# tick-wifi-mk-1_0.net
KiCad netlist of a schematic drawn in EAGLE
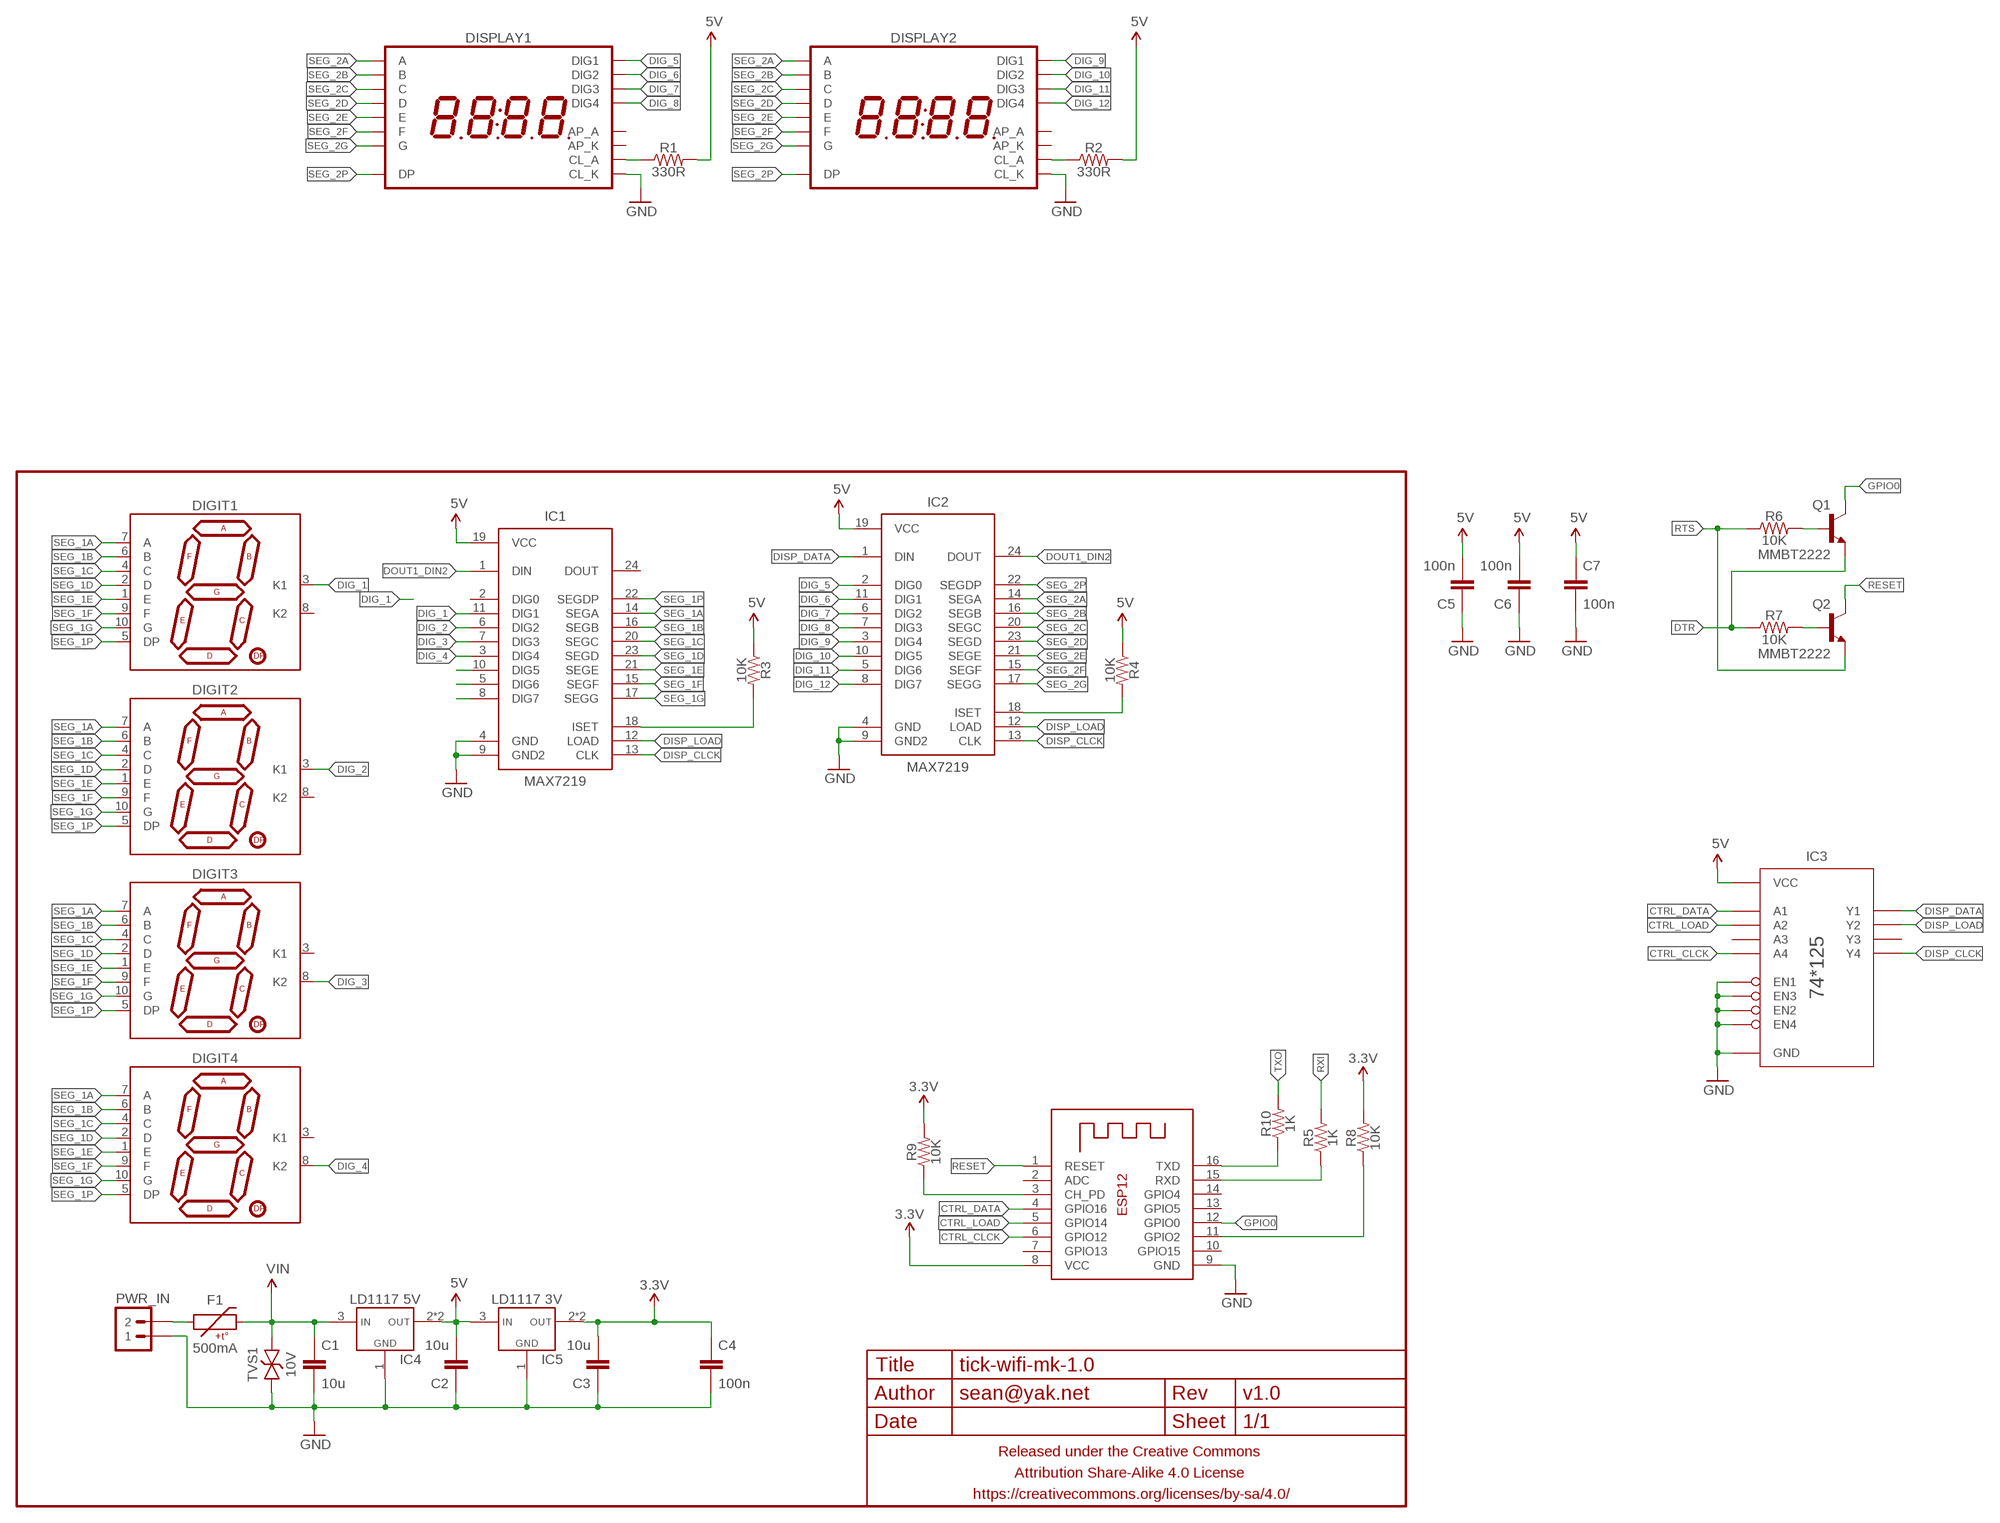
[diagram p0: schematic, sheet 1]

(export (version "E")
  (design (tool "Eeschema 10.0.6"))
  (components
    (comp (ref "C1")
      (value "10u")
      (footprint "eagle-import:C1210")
      (libsource (lib "eagle-import") (part "CAPACITOR-CERAMICC1210"))
    )
    (comp (ref "C2")
      (value "10u")
      (footprint "eagle-import:C1210")
      (libsource (lib "eagle-import") (part "CAPACITOR-CERAMICC1210"))
    )
    (comp (ref "C3")
      (value "10u")
      (footprint "eagle-import:C1210")
      (libsource (lib "eagle-import") (part "CAPACITOR-CERAMICC1210"))
    )
    (comp (ref "C4")
      (value "100n")
      (footprint "eagle-import:C0603")
      (libsource (lib "eagle-import") (part "CAPACITOR-CERAMICC0603"))
    )
    (comp (ref "C5")
      (value "100n")
      (footprint "eagle-import:C0603")
      (libsource (lib "eagle-import") (part "CAPACITOR-CERAMICC0603"))
    )
    (comp (ref "C6")
      (value "100n")
      (footprint "eagle-import:C0603")
      (libsource (lib "eagle-import") (part "CAPACITOR-CERAMICC0603"))
    )
    (comp (ref "C7")
      (value "100n")
      (footprint "eagle-import:C0603")
      (libsource (lib "eagle-import") (part "CAPACITOR-CERAMICC0603"))
    )
    (comp (ref "DIGIT1")
      (value "7SEG_1DIGPTH-25.4MM-BARE")
      (footprint "eagle-import:7SEG_1DIG_25.4MM_NOSILK")
      (libsource (lib "eagle-import") (part "7SEG_1DIGPTH-25.4MM-BARE"))
    )
    (comp (ref "DIGIT2")
      (value "7SEG_1DIGPTH-25.4MM-BARE")
      (footprint "eagle-import:7SEG_1DIG_25.4MM_NOSILK")
      (libsource (lib "eagle-import") (part "7SEG_1DIGPTH-25.4MM-BARE"))
    )
    (comp (ref "DIGIT3")
      (value "7SEG_1DIGPTH-25.4MM-BARE")
      (footprint "eagle-import:7SEG_1DIG_25.4MM_NOSILK")
      (libsource (lib "eagle-import") (part "7SEG_1DIGPTH-25.4MM-BARE"))
    )
    (comp (ref "DIGIT4")
      (value "7SEG_1DIGPTH-25.4MM-BARE")
      (footprint "eagle-import:7SEG_1DIG_25.4MM_NOSILK")
      (libsource (lib "eagle-import") (part "7SEG_1DIGPTH-25.4MM-BARE"))
    )
    (comp (ref "DISPLAY1")
      (value "7SEG_4DIGIT_COLON_APOS")
      (footprint "eagle-import:7SEG_4DIG_10MM")
      (libsource (lib "eagle-import") (part "7SEG_4DIGIT_COLON_APOS"))
    )
    (comp (ref "DISPLAY2")
      (value "7SEG_4DIGIT_COLON_APOS")
      (footprint "eagle-import:7SEG_4DIG_10MM")
      (libsource (lib "eagle-import") (part "7SEG_4DIGIT_COLON_APOS"))
    )
    (comp (ref "F1")
      (value "500mA")
      (footprint "eagle-import:PTC-1210")
      (libsource (lib "eagle-import") (part "PTCPTC-1210"))
    )
    (comp (ref "FRAME1")
      (value "FRAME-LETTERNO_PACKAGE")
      (footprint "eagle-import:DUMMY")
      (fields (field (name "DESIGNER") "sean@yak.net") (field (name "VERSION") "v1.0"))
      (libsource (lib "eagle-import") (part "FRAME-LETTERNO_PACKAGE"))
    )
    (comp (ref "IC1")
      (value "MAX7219")
      (footprint "eagle-import:SO24W")
      (libsource (lib "eagle-import") (part "MAX7219SOIC-W"))
    )
    (comp (ref "IC2")
      (value "MAX7219")
      (footprint "eagle-import:SO24W")
      (libsource (lib "eagle-import") (part "MAX7219SOIC-W"))
    )
    (comp (ref "IC3")
      (value "74HC125")
      (footprint "eagle-import:SO14")
      (libsource (lib "eagle-import") (part "74125SOIC14"))
    )
    (comp (ref "IC4")
      (value "LD1117 5V")
      (footprint "eagle-import:SOT223")
      (libsource (lib "eagle-import") (part "VREG_1117SOT223"))
    )
    (comp (ref "IC5")
      (value "LD1117 3V")
      (footprint "eagle-import:SOT223")
      (libsource (lib "eagle-import") (part "VREG_1117SOT223"))
    )
    (comp (ref "PWR_IN")
      (value "M02PTH-CENTERED-R+")
      (footprint "eagle-import:1X02-CENTER-R+")
      (libsource (lib "eagle-import") (part "M02PTH-CENTERED-R+"))
    )
    (comp (ref "Q1")
      (value "MMBT2222")
      (footprint "eagle-import:SOT23")
      (libsource (lib "eagle-import") (part "TRANSISTOR_NPNMMBT2222A"))
    )
    (comp (ref "Q2")
      (value "MMBT2222")
      (footprint "eagle-import:SOT23")
      (libsource (lib "eagle-import") (part "TRANSISTOR_NPNMMBT2222A"))
    )
    (comp (ref "R1")
      (value "330R")
      (footprint "eagle-import:R0805")
      (libsource (lib "eagle-import") (part "RESISTORR0805"))
    )
    (comp (ref "R2")
      (value "330R")
      (footprint "eagle-import:R0805")
      (libsource (lib "eagle-import") (part "RESISTORR0805"))
    )
    (comp (ref "R3")
      (value "10K")
      (footprint "eagle-import:R0603")
      (libsource (lib "eagle-import") (part "RESISTORR0603"))
    )
    (comp (ref "R4")
      (value "10K")
      (footprint "eagle-import:R0603")
      (libsource (lib "eagle-import") (part "RESISTORR0603"))
    )
    (comp (ref "R5")
      (value "1K")
      (footprint "eagle-import:R0603")
      (libsource (lib "eagle-import") (part "RESISTORR0603"))
    )
    (comp (ref "R6")
      (value "10K")
      (footprint "eagle-import:R0603")
      (libsource (lib "eagle-import") (part "RESISTORR0603"))
    )
    (comp (ref "R7")
      (value "10K")
      (footprint "eagle-import:R0603")
      (libsource (lib "eagle-import") (part "RESISTORR0603"))
    )
    (comp (ref "R8")
      (value "10K")
      (footprint "eagle-import:R0603")
      (libsource (lib "eagle-import") (part "RESISTORR0603"))
    )
    (comp (ref "R9")
      (value "10K")
      (footprint "eagle-import:R0603")
      (libsource (lib "eagle-import") (part "RESISTORR0603"))
    )
    (comp (ref "R10")
      (value "1K")
      (footprint "eagle-import:R0603")
      (libsource (lib "eagle-import") (part "RESISTORR0603"))
    )
    (comp (ref "TVS1")
      (value "10V")
      (footprint "eagle-import:SMA-DIODE-TVS-BIDIR")
      (libsource (lib "eagle-import") (part "TVSSMA"))
    )
    (comp (ref "U1")
      (value "ESP-12")
      (footprint "eagle-import:ESP-12")
      (libsource (lib "eagle-import") (part "ESP-12"))
    )
  )
  (nets
    (net (code "1") (name "3.3V") (class "Default")
      (node (ref "C3") (pin "2") (pinfunction "2_2") (pintype "passive"))
      (node (ref "C4") (pin "1") (pinfunction "1_1") (pintype "passive"))
      (node (ref "IC5") (pin "2") (pinfunction "VOUT_2") (pintype "bidirectional"))
      (node (ref "IC5") (pin "4") (pinfunction "VOUT_4") (pintype "bidirectional"))
      (node (ref "R8") (pin "2") (pinfunction "2_2") (pintype "passive"))
      (node (ref "R9") (pin "2") (pinfunction "2_2") (pintype "passive"))
      (node (ref "U1") (pin "8") (pinfunction "VCC_8") (pintype "power_in"))
    )
    (net (code "2") (name "5V") (class "Default")
      (node (ref "C2") (pin "2") (pinfunction "2_2") (pintype "passive"))
      (node (ref "C5") (pin "2") (pinfunction "2_2") (pintype "passive"))
      (node (ref "C6") (pin "2") (pinfunction "2_2") (pintype "passive"))
      (node (ref "C7") (pin "1") (pinfunction "1_1") (pintype "passive"))
      (node (ref "IC1") (pin "19") (pinfunction "VCC_19") (pintype "bidirectional"))
      (node (ref "IC2") (pin "19") (pinfunction "VCC_19") (pintype "bidirectional"))
      (node (ref "IC3") (pin "14") (pinfunction "VCC_14") (pintype "bidirectional"))
      (node (ref "IC4") (pin "2") (pinfunction "VOUT_2") (pintype "bidirectional"))
      (node (ref "IC4") (pin "4") (pinfunction "VOUT_4") (pintype "bidirectional"))
      (node (ref "IC5") (pin "3") (pinfunction "VIN_3") (pintype "bidirectional"))
      (node (ref "R1") (pin "2") (pinfunction "2_2") (pintype "passive"))
      (node (ref "R2") (pin "2") (pinfunction "2_2") (pintype "passive"))
      (node (ref "R3") (pin "1") (pinfunction "1_1") (pintype "passive"))
      (node (ref "R4") (pin "1") (pinfunction "1_1") (pintype "passive"))
    )
    (net (code "3") (name "CTRL_CLCK") (class "Default")
      (node (ref "IC3") (pin "12") (pinfunction "A4_12") (pintype "bidirectional"))
      (node (ref "U1") (pin "6") (pinfunction "GPIO12_6") (pintype "bidirectional"))
    )
    (net (code "4") (name "CTRL_DATA") (class "Default")
      (node (ref "IC3") (pin "2") (pinfunction "A1_2") (pintype "bidirectional"))
      (node (ref "U1") (pin "4") (pinfunction "GPIO16_4") (pintype "bidirectional"))
    )
    (net (code "5") (name "CTRL_LOAD") (class "Default")
      (node (ref "IC3") (pin "5") (pinfunction "A2_5") (pintype "bidirectional"))
      (node (ref "U1") (pin "5") (pinfunction "GPIO14_5") (pintype "bidirectional"))
    )
    (net (code "6") (name "DIG_1") (class "Default")
      (node (ref "DIGIT1") (pin "3") (pinfunction "K1_3") (pintype "bidirectional"))
      (node (ref "IC1") (pin "11") (pinfunction "DIG1_11") (pintype "bidirectional"))
    )
    (net (code "7") (name "DIG_2") (class "Default")
      (node (ref "DIGIT2") (pin "3") (pinfunction "K1_3") (pintype "bidirectional"))
      (node (ref "IC1") (pin "6") (pinfunction "DIG2_6") (pintype "bidirectional"))
    )
    (net (code "8") (name "DIG_3") (class "Default")
      (node (ref "DIGIT3") (pin "8") (pinfunction "K2_8") (pintype "bidirectional"))
      (node (ref "IC1") (pin "7") (pinfunction "DIG3_7") (pintype "bidirectional"))
    )
    (net (code "9") (name "DIG_4") (class "Default")
      (node (ref "DIGIT4") (pin "8") (pinfunction "K2_8") (pintype "bidirectional"))
      (node (ref "IC1") (pin "3") (pinfunction "DIG4_3") (pintype "bidirectional"))
    )
    (net (code "10") (name "DIG_5") (class "Default")
      (node (ref "DISPLAY1") (pin "1") (pinfunction "DIG1_1") (pintype "passive"))
      (node (ref "IC2") (pin "2") (pinfunction "DIG0_2") (pintype "bidirectional"))
    )
    (net (code "11") (name "DIG_6") (class "Default")
      (node (ref "DISPLAY1") (pin "2") (pinfunction "DIG2_2") (pintype "passive"))
      (node (ref "IC2") (pin "11") (pinfunction "DIG1_11") (pintype "bidirectional"))
    )
    (net (code "12") (name "DIG_7") (class "Default")
      (node (ref "DISPLAY1") (pin "6") (pinfunction "DIG3_6") (pintype "passive"))
      (node (ref "IC2") (pin "6") (pinfunction "DIG2_6") (pintype "bidirectional"))
    )
    (net (code "13") (name "DIG_8") (class "Default")
      (node (ref "DISPLAY1") (pin "8") (pinfunction "DIG4_8") (pintype "passive"))
      (node (ref "IC2") (pin "7") (pinfunction "DIG3_7") (pintype "bidirectional"))
    )
    (net (code "14") (name "DIG_9") (class "Default")
      (node (ref "DISPLAY2") (pin "1") (pinfunction "DIG1_1") (pintype "passive"))
      (node (ref "IC2") (pin "3") (pinfunction "DIG4_3") (pintype "bidirectional"))
    )
    (net (code "15") (name "DIG_10") (class "Default")
      (node (ref "DISPLAY2") (pin "2") (pinfunction "DIG2_2") (pintype "passive"))
      (node (ref "IC2") (pin "10") (pinfunction "DIG5_10") (pintype "bidirectional"))
    )
    (net (code "16") (name "DIG_11") (class "Default")
      (node (ref "DISPLAY2") (pin "6") (pinfunction "DIG3_6") (pintype "passive"))
      (node (ref "IC2") (pin "5") (pinfunction "DIG6_5") (pintype "bidirectional"))
    )
    (net (code "17") (name "DIG_12") (class "Default")
      (node (ref "DISPLAY2") (pin "8") (pinfunction "DIG4_8") (pintype "passive"))
      (node (ref "IC2") (pin "8") (pinfunction "DIG7_8") (pintype "bidirectional"))
    )
    (net (code "18") (name "DISP_CLCK") (class "Default")
      (node (ref "IC1") (pin "13") (pinfunction "CLK_13") (pintype "bidirectional"))
      (node (ref "IC2") (pin "13") (pinfunction "CLK_13") (pintype "bidirectional"))
      (node (ref "IC3") (pin "11") (pinfunction "Y4_11") (pintype "bidirectional"))
    )
    (net (code "19") (name "DISP_DATA") (class "Default")
      (node (ref "IC2") (pin "1") (pinfunction "DIN_1") (pintype "bidirectional"))
      (node (ref "IC3") (pin "3") (pinfunction "Y1_3") (pintype "bidirectional"))
    )
    (net (code "20") (name "DISP_LOAD") (class "Default")
      (node (ref "IC1") (pin "12") (pinfunction "LOAD_12") (pintype "bidirectional"))
      (node (ref "IC2") (pin "12") (pinfunction "LOAD_12") (pintype "bidirectional"))
      (node (ref "IC3") (pin "6") (pinfunction "Y2_6") (pintype "bidirectional"))
    )
    (net (code "21") (name "DOUT1_DIN2") (class "Default")
      (node (ref "IC1") (pin "1") (pinfunction "DIN_1") (pintype "bidirectional"))
      (node (ref "IC2") (pin "24") (pinfunction "DOUT_24") (pintype "bidirectional"))
    )
    (net (code "22") (name "DTR") (class "Default")
      (node (ref "Q1") (pin "2") (pinfunction "E_2") (pintype "passive"))
      (node (ref "R7") (pin "1") (pinfunction "1_1") (pintype "passive"))
    )
    (net (code "23") (name "GND") (class "Default")
      (node (ref "C1") (pin "2") (pinfunction "2_2") (pintype "passive"))
      (node (ref "C2") (pin "1") (pinfunction "1_1") (pintype "passive"))
      (node (ref "C3") (pin "1") (pinfunction "1_1") (pintype "passive"))
      (node (ref "C4") (pin "2") (pinfunction "2_2") (pintype "passive"))
      (node (ref "C5") (pin "1") (pinfunction "1_1") (pintype "passive"))
      (node (ref "C6") (pin "1") (pinfunction "1_1") (pintype "passive"))
      (node (ref "C7") (pin "2") (pinfunction "2_2") (pintype "passive"))
      (node (ref "DISPLAY1") (pin "12") (pinfunction "CL_K_12") (pintype "passive"))
      (node (ref "DISPLAY2") (pin "12") (pinfunction "CL_K_12") (pintype "passive"))
      (node (ref "IC1") (pin "4") (pinfunction "GND_4") (pintype "bidirectional"))
      (node (ref "IC1") (pin "9") (pinfunction "GND2_9") (pintype "bidirectional"))
      (node (ref "IC2") (pin "4") (pinfunction "GND_4") (pintype "bidirectional"))
      (node (ref "IC2") (pin "9") (pinfunction "GND2_9") (pintype "bidirectional"))
      (node (ref "IC3") (pin "1") (pinfunction "EN1_1") (pintype "bidirectional"))
      (node (ref "IC3") (pin "10") (pinfunction "EN3_10") (pintype "bidirectional"))
      (node (ref "IC3") (pin "13") (pinfunction "EN4_13") (pintype "bidirectional"))
      (node (ref "IC3") (pin "4") (pinfunction "EN2_4") (pintype "bidirectional"))
      (node (ref "IC3") (pin "7") (pinfunction "GND_7") (pintype "bidirectional"))
      (node (ref "IC4") (pin "1") (pinfunction "GND_1") (pintype "bidirectional"))
      (node (ref "IC5") (pin "1") (pinfunction "GND_1") (pintype "bidirectional"))
      (node (ref "PWR_IN") (pin "1") (pinfunction "1_1") (pintype "passive"))
      (node (ref "TVS1") (pin "1") (pinfunction "1_1") (pintype "passive"))
      (node (ref "U1") (pin "9") (pinfunction "GND_9") (pintype "power_in"))
    )
    (net (code "24") (name "GPIO0") (class "Default")
      (node (ref "Q1") (pin "3") (pinfunction "C_3") (pintype "passive"))
      (node (ref "U1") (pin "12") (pinfunction "GPIO0_12") (pintype "bidirectional"))
    )
    (net (code "25") (name "Net-(DISPLAY1-CL_A)") (class "Default")
      (node (ref "DISPLAY1") (pin "4") (pinfunction "CL_A_4") (pintype "passive"))
      (node (ref "R1") (pin "1") (pinfunction "1_1") (pintype "passive"))
    )
    (net (code "26") (name "Net-(DISPLAY2-CL_A)") (class "Default")
      (node (ref "DISPLAY2") (pin "4") (pinfunction "CL_A_4") (pintype "passive"))
      (node (ref "R2") (pin "1") (pinfunction "1_1") (pintype "passive"))
    )
    (net (code "27") (name "Net-(F1-Pad1)") (class "Default")
      (node (ref "F1") (pin "1") (pinfunction "1_1") (pintype "passive"))
      (node (ref "PWR_IN") (pin "2") (pinfunction "2_2") (pintype "passive"))
    )
    (net (code "28") (name "Net-(IC1-ISET)") (class "Default")
      (node (ref "IC1") (pin "18") (pinfunction "ISET_18") (pintype "bidirectional"))
      (node (ref "R3") (pin "2") (pinfunction "2_2") (pintype "passive"))
    )
    (net (code "29") (name "Net-(IC2-ISET)") (class "Default")
      (node (ref "IC2") (pin "18") (pinfunction "ISET_18") (pintype "bidirectional"))
      (node (ref "R4") (pin "2") (pinfunction "2_2") (pintype "passive"))
    )
    (net (code "30") (name "Net-(Q1-B)") (class "Default")
      (node (ref "Q1") (pin "1") (pinfunction "B_1") (pintype "passive"))
      (node (ref "R6") (pin "2") (pinfunction "2_2") (pintype "passive"))
    )
    (net (code "31") (name "Net-(Q2-B)") (class "Default")
      (node (ref "Q2") (pin "1") (pinfunction "B_1") (pintype "passive"))
      (node (ref "R7") (pin "2") (pinfunction "2_2") (pintype "passive"))
    )
    (net (code "32") (name "Net-(U1-CH_PD)") (class "Default")
      (node (ref "R9") (pin "1") (pinfunction "1_1") (pintype "passive"))
      (node (ref "U1") (pin "3") (pinfunction "CH_PD_3") (pintype "input"))
    )
    (net (code "33") (name "Net-(U1-GPIO2)") (class "Default")
      (node (ref "R8") (pin "1") (pinfunction "1_1") (pintype "passive"))
      (node (ref "U1") (pin "11") (pinfunction "GPIO2_11") (pintype "bidirectional"))
    )
    (net (code "34") (name "Net-(U1-RXD)") (class "Default")
      (node (ref "R5") (pin "1") (pinfunction "1_1") (pintype "passive"))
      (node (ref "U1") (pin "15") (pinfunction "RXD_15") (pintype "input"))
    )
    (net (code "35") (name "Net-(U1-TXD)") (class "Default")
      (node (ref "R10") (pin "1") (pinfunction "1_1") (pintype "passive"))
      (node (ref "U1") (pin "16") (pinfunction "TXD_16") (pintype "output"))
    )
    (net (code "36") (name "RESET") (class "Default")
      (node (ref "Q2") (pin "3") (pinfunction "C_3") (pintype "passive"))
      (node (ref "U1") (pin "1") (pinfunction "RESET_1") (pintype "input"))
    )
    (net (code "37") (name "RTS") (class "Default")
      (node (ref "Q2") (pin "2") (pinfunction "E_2") (pintype "passive"))
      (node (ref "R6") (pin "1") (pinfunction "1_1") (pintype "passive"))
    )
    (net (code "38") (name "RXI") (class "Default")
      (node (ref "R5") (pin "2") (pinfunction "2_2") (pintype "passive"))
    )
    (net (code "39") (name "SEG_1A") (class "Default")
      (node (ref "DIGIT1") (pin "7") (pinfunction "A_7") (pintype "bidirectional"))
      (node (ref "DIGIT2") (pin "7") (pinfunction "A_7") (pintype "bidirectional"))
      (node (ref "DIGIT3") (pin "7") (pinfunction "A_7") (pintype "bidirectional"))
      (node (ref "DIGIT4") (pin "7") (pinfunction "A_7") (pintype "bidirectional"))
      (node (ref "IC1") (pin "14") (pinfunction "SEGA_14") (pintype "bidirectional"))
    )
    (net (code "40") (name "SEG_1B") (class "Default")
      (node (ref "DIGIT1") (pin "6") (pinfunction "B_6") (pintype "bidirectional"))
      (node (ref "DIGIT2") (pin "6") (pinfunction "B_6") (pintype "bidirectional"))
      (node (ref "DIGIT3") (pin "6") (pinfunction "B_6") (pintype "bidirectional"))
      (node (ref "DIGIT4") (pin "6") (pinfunction "B_6") (pintype "bidirectional"))
      (node (ref "IC1") (pin "16") (pinfunction "SEGB_16") (pintype "bidirectional"))
    )
    (net (code "41") (name "SEG_1C") (class "Default")
      (node (ref "DIGIT1") (pin "4") (pinfunction "C_4") (pintype "bidirectional"))
      (node (ref "DIGIT2") (pin "4") (pinfunction "C_4") (pintype "bidirectional"))
      (node (ref "DIGIT3") (pin "4") (pinfunction "C_4") (pintype "bidirectional"))
      (node (ref "DIGIT4") (pin "4") (pinfunction "C_4") (pintype "bidirectional"))
      (node (ref "IC1") (pin "20") (pinfunction "SEGC_20") (pintype "bidirectional"))
    )
    (net (code "42") (name "SEG_1D") (class "Default")
      (node (ref "DIGIT1") (pin "2") (pinfunction "D_2") (pintype "bidirectional"))
      (node (ref "DIGIT2") (pin "2") (pinfunction "D_2") (pintype "bidirectional"))
      (node (ref "DIGIT3") (pin "2") (pinfunction "D_2") (pintype "bidirectional"))
      (node (ref "DIGIT4") (pin "2") (pinfunction "D_2") (pintype "bidirectional"))
      (node (ref "IC1") (pin "23") (pinfunction "SEGD_23") (pintype "bidirectional"))
    )
    (net (code "43") (name "SEG_1E") (class "Default")
      (node (ref "DIGIT1") (pin "1") (pinfunction "E_1") (pintype "bidirectional"))
      (node (ref "DIGIT2") (pin "1") (pinfunction "E_1") (pintype "bidirectional"))
      (node (ref "DIGIT3") (pin "1") (pinfunction "E_1") (pintype "bidirectional"))
      (node (ref "DIGIT4") (pin "1") (pinfunction "E_1") (pintype "bidirectional"))
      (node (ref "IC1") (pin "21") (pinfunction "SEGE_21") (pintype "bidirectional"))
    )
    (net (code "44") (name "SEG_1F") (class "Default")
      (node (ref "DIGIT1") (pin "9") (pinfunction "F_9") (pintype "bidirectional"))
      (node (ref "DIGIT2") (pin "9") (pinfunction "F_9") (pintype "bidirectional"))
      (node (ref "DIGIT3") (pin "9") (pinfunction "F_9") (pintype "bidirectional"))
      (node (ref "DIGIT4") (pin "9") (pinfunction "F_9") (pintype "bidirectional"))
      (node (ref "IC1") (pin "15") (pinfunction "SEGF_15") (pintype "bidirectional"))
    )
    (net (code "45") (name "SEG_1G") (class "Default")
      (node (ref "DIGIT1") (pin "10") (pinfunction "G_10") (pintype "bidirectional"))
      (node (ref "DIGIT2") (pin "10") (pinfunction "G_10") (pintype "bidirectional"))
      (node (ref "DIGIT3") (pin "10") (pinfunction "G_10") (pintype "bidirectional"))
      (node (ref "DIGIT4") (pin "10") (pinfunction "G_10") (pintype "bidirectional"))
      (node (ref "IC1") (pin "17") (pinfunction "SEGG_17") (pintype "bidirectional"))
    )
    (net (code "46") (name "SEG_1P") (class "Default")
      (node (ref "DIGIT1") (pin "5") (pinfunction "DP_5") (pintype "bidirectional"))
      (node (ref "DIGIT2") (pin "5") (pinfunction "DP_5") (pintype "bidirectional"))
      (node (ref "DIGIT3") (pin "5") (pinfunction "DP_5") (pintype "bidirectional"))
      (node (ref "DIGIT4") (pin "5") (pinfunction "DP_5") (pintype "bidirectional"))
      (node (ref "IC1") (pin "22") (pinfunction "SEGDP_22") (pintype "bidirectional"))
    )
    (net (code "47") (name "SEG_2A") (class "Default")
      (node (ref "DISPLAY1") (pin "14") (pinfunction "A_14") (pintype "passive"))
      (node (ref "DISPLAY2") (pin "14") (pinfunction "A_14") (pintype "passive"))
      (node (ref "IC2") (pin "14") (pinfunction "SEGA_14") (pintype "bidirectional"))
    )
    (net (code "48") (name "SEG_2B") (class "Default")
      (node (ref "DISPLAY1") (pin "16") (pinfunction "B_16") (pintype "passive"))
      (node (ref "DISPLAY2") (pin "16") (pinfunction "B_16") (pintype "passive"))
      (node (ref "IC2") (pin "16") (pinfunction "SEGB_16") (pintype "bidirectional"))
    )
    (net (code "49") (name "SEG_2C") (class "Default")
      (node (ref "DISPLAY1") (pin "13") (pinfunction "C_13") (pintype "passive"))
      (node (ref "DISPLAY2") (pin "13") (pinfunction "C_13") (pintype "passive"))
      (node (ref "IC2") (pin "20") (pinfunction "SEGC_20") (pintype "bidirectional"))
    )
    (net (code "50") (name "SEG_2D") (class "Default")
      (node (ref "DISPLAY1") (pin "3") (pinfunction "D_3") (pintype "passive"))
      (node (ref "DISPLAY2") (pin "3") (pinfunction "D_3") (pintype "passive"))
      (node (ref "IC2") (pin "23") (pinfunction "SEGD_23") (pintype "bidirectional"))
    )
    (net (code "51") (name "SEG_2E") (class "Default")
      (node (ref "DISPLAY1") (pin "5") (pinfunction "E_5") (pintype "passive"))
      (node (ref "DISPLAY2") (pin "5") (pinfunction "E_5") (pintype "passive"))
      (node (ref "IC2") (pin "21") (pinfunction "SEGE_21") (pintype "bidirectional"))
    )
    (net (code "52") (name "SEG_2F") (class "Default")
      (node (ref "DISPLAY1") (pin "11") (pinfunction "F_11") (pintype "passive"))
      (node (ref "DISPLAY2") (pin "11") (pinfunction "F_11") (pintype "passive"))
      (node (ref "IC2") (pin "15") (pinfunction "SEGF_15") (pintype "bidirectional"))
    )
    (net (code "53") (name "SEG_2G") (class "Default")
      (node (ref "DISPLAY1") (pin "15") (pinfunction "G_15") (pintype "passive"))
      (node (ref "DISPLAY2") (pin "15") (pinfunction "G_15") (pintype "passive"))
      (node (ref "IC2") (pin "17") (pinfunction "SEGG_17") (pintype "bidirectional"))
    )
    (net (code "54") (name "SEG_2P") (class "Default")
      (node (ref "DISPLAY1") (pin "7") (pinfunction "DP_7") (pintype "passive"))
      (node (ref "DISPLAY2") (pin "7") (pinfunction "DP_7") (pintype "passive"))
      (node (ref "IC2") (pin "22") (pinfunction "SEGDP_22") (pintype "bidirectional"))
    )
    (net (code "55") (name "TXO") (class "Default")
      (node (ref "R10") (pin "2") (pinfunction "2_2") (pintype "passive"))
    )
    (net (code "56") (name "VIN") (class "Default")
      (node (ref "C1") (pin "1") (pinfunction "1_1") (pintype "passive"))
      (node (ref "F1") (pin "2") (pinfunction "2_2") (pintype "passive"))
      (node (ref "IC4") (pin "3") (pinfunction "VIN_3") (pintype "bidirectional"))
      (node (ref "TVS1") (pin "2") (pinfunction "2_2") (pintype "passive"))
    )
    (net (code "57") (name "unconnected-(DIGIT1-K2-Pad8)") (class "Default")
      (node (ref "DIGIT1") (pin "8") (pinfunction "K2_8") (pintype "bidirectional"))
    )
    (net (code "58") (name "unconnected-(DIGIT2-K2-Pad8)") (class "Default")
      (node (ref "DIGIT2") (pin "8") (pinfunction "K2_8") (pintype "bidirectional"))
    )
    (net (code "59") (name "unconnected-(DIGIT3-K1-Pad3)") (class "Default")
      (node (ref "DIGIT3") (pin "3") (pinfunction "K1_3") (pintype "bidirectional"))
    )
    (net (code "60") (name "unconnected-(DIGIT4-K1-Pad3)") (class "Default")
      (node (ref "DIGIT4") (pin "3") (pinfunction "K1_3") (pintype "bidirectional"))
    )
    (net (code "61") (name "unconnected-(DISPLAY1-AP_A-Pad10)") (class "Default")
      (node (ref "DISPLAY1") (pin "10") (pinfunction "AP_A_10") (pintype "bidirectional"))
    )
    (net (code "62") (name "unconnected-(DISPLAY1-AP_K-Pad9)") (class "Default")
      (node (ref "DISPLAY1") (pin "9") (pinfunction "AP_K_9") (pintype "bidirectional"))
    )
    (net (code "63") (name "unconnected-(DISPLAY2-AP_A-Pad10)") (class "Default")
      (node (ref "DISPLAY2") (pin "10") (pinfunction "AP_A_10") (pintype "bidirectional"))
    )
    (net (code "64") (name "unconnected-(DISPLAY2-AP_K-Pad9)") (class "Default")
      (node (ref "DISPLAY2") (pin "9") (pinfunction "AP_K_9") (pintype "bidirectional"))
    )
    (net (code "65") (name "unconnected-(IC1-DIG0-Pad2)") (class "Default")
      (node (ref "IC1") (pin "2") (pinfunction "DIG0_2") (pintype "bidirectional"))
    )
    (net (code "66") (name "unconnected-(IC1-DIG5-Pad10)") (class "Default")
      (node (ref "IC1") (pin "10") (pinfunction "DIG5_10") (pintype "bidirectional"))
    )
    (net (code "67") (name "unconnected-(IC1-DIG6-Pad5)") (class "Default")
      (node (ref "IC1") (pin "5") (pinfunction "DIG6_5") (pintype "bidirectional"))
    )
    (net (code "68") (name "unconnected-(IC1-DIG7-Pad8)") (class "Default")
      (node (ref "IC1") (pin "8") (pinfunction "DIG7_8") (pintype "bidirectional"))
    )
    (net (code "69") (name "unconnected-(IC1-DOUT-Pad24)") (class "Default")
      (node (ref "IC1") (pin "24") (pinfunction "DOUT_24") (pintype "bidirectional"))
    )
    (net (code "70") (name "unconnected-(IC3-A3-Pad9)") (class "Default")
      (node (ref "IC3") (pin "9") (pinfunction "A3_9") (pintype "bidirectional"))
    )
    (net (code "71") (name "unconnected-(IC3-Y3-Pad8)") (class "Default")
      (node (ref "IC3") (pin "8") (pinfunction "Y3_8") (pintype "bidirectional"))
    )
    (net (code "72") (name "unconnected-(U1-ADC-Pad2)") (class "Default")
      (node (ref "U1") (pin "2") (pinfunction "ADC_2") (pintype "passive"))
    )
    (net (code "73") (name "unconnected-(U1-GPIO4-Pad14)") (class "Default")
      (node (ref "U1") (pin "14") (pinfunction "GPIO4_14") (pintype "bidirectional"))
    )
    (net (code "74") (name "unconnected-(U1-GPIO5-Pad13)") (class "Default")
      (node (ref "U1") (pin "13") (pinfunction "GPIO5_13") (pintype "bidirectional"))
    )
    (net (code "75") (name "unconnected-(U1-GPIO13-Pad7)") (class "Default")
      (node (ref "U1") (pin "7") (pinfunction "GPIO13_7") (pintype "bidirectional"))
    )
    (net (code "76") (name "unconnected-(U1-GPIO15-Pad10)") (class "Default")
      (node (ref "U1") (pin "10") (pinfunction "GPIO15_10") (pintype "bidirectional"))
    )
  )
)
